# TEMPLATE_REG.net
KiCad netlist of a schematic drawn in Altium Designer
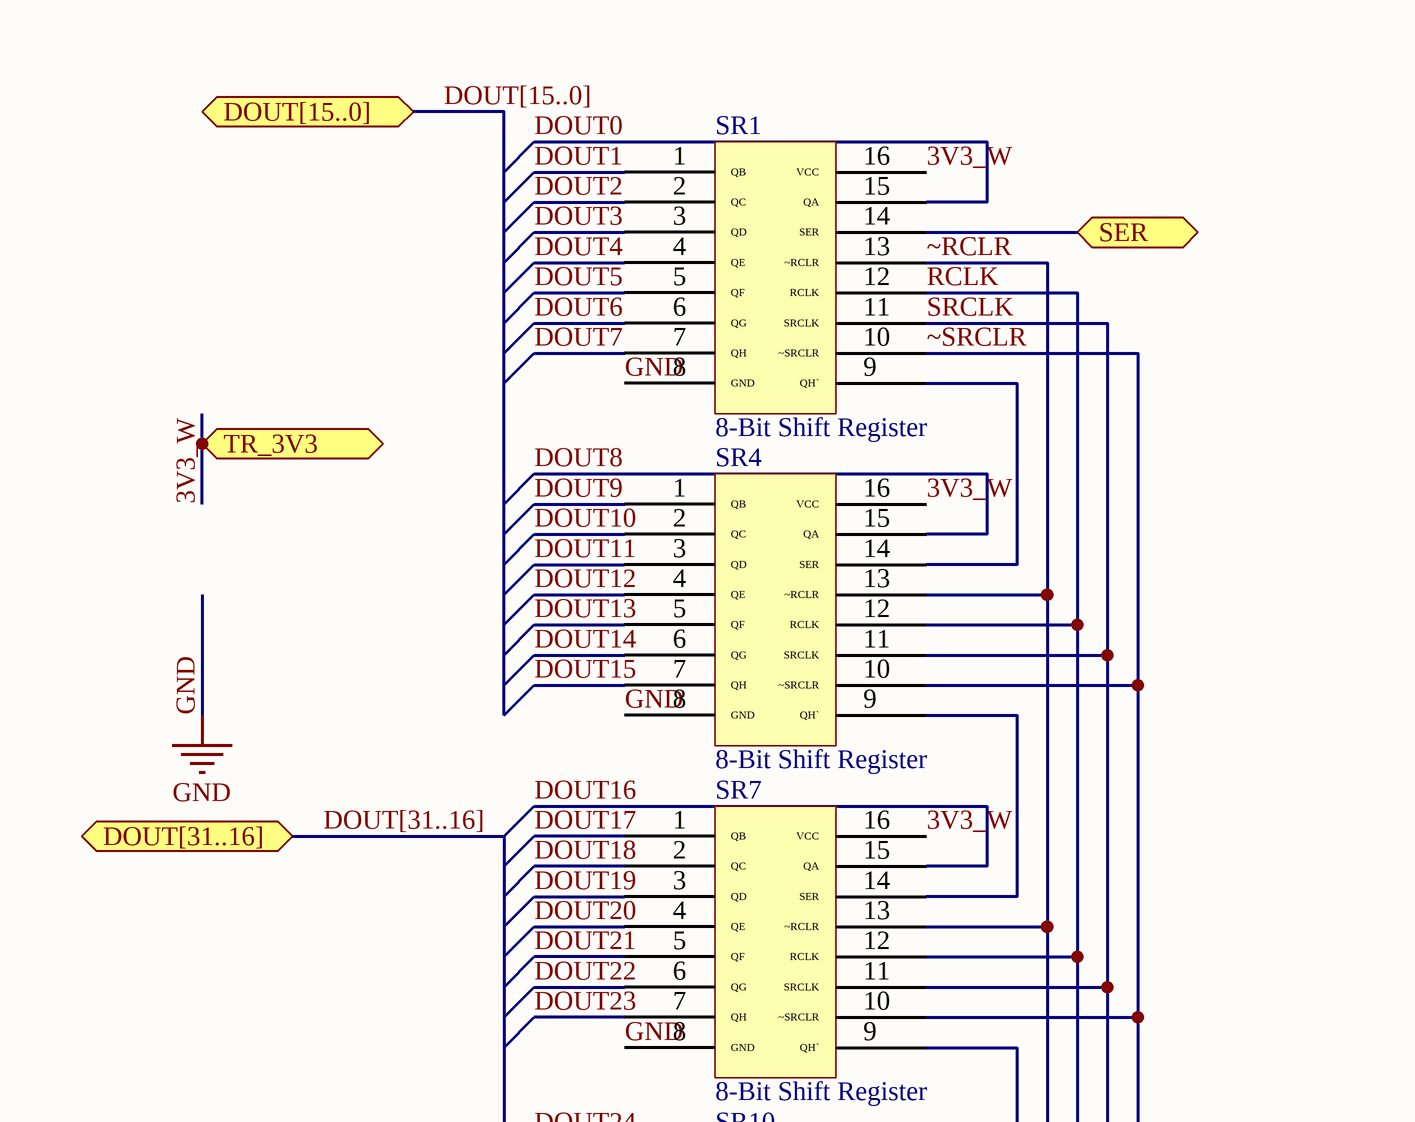
[diagram p0: TEMPLATE_REG.SchDoc, top left]
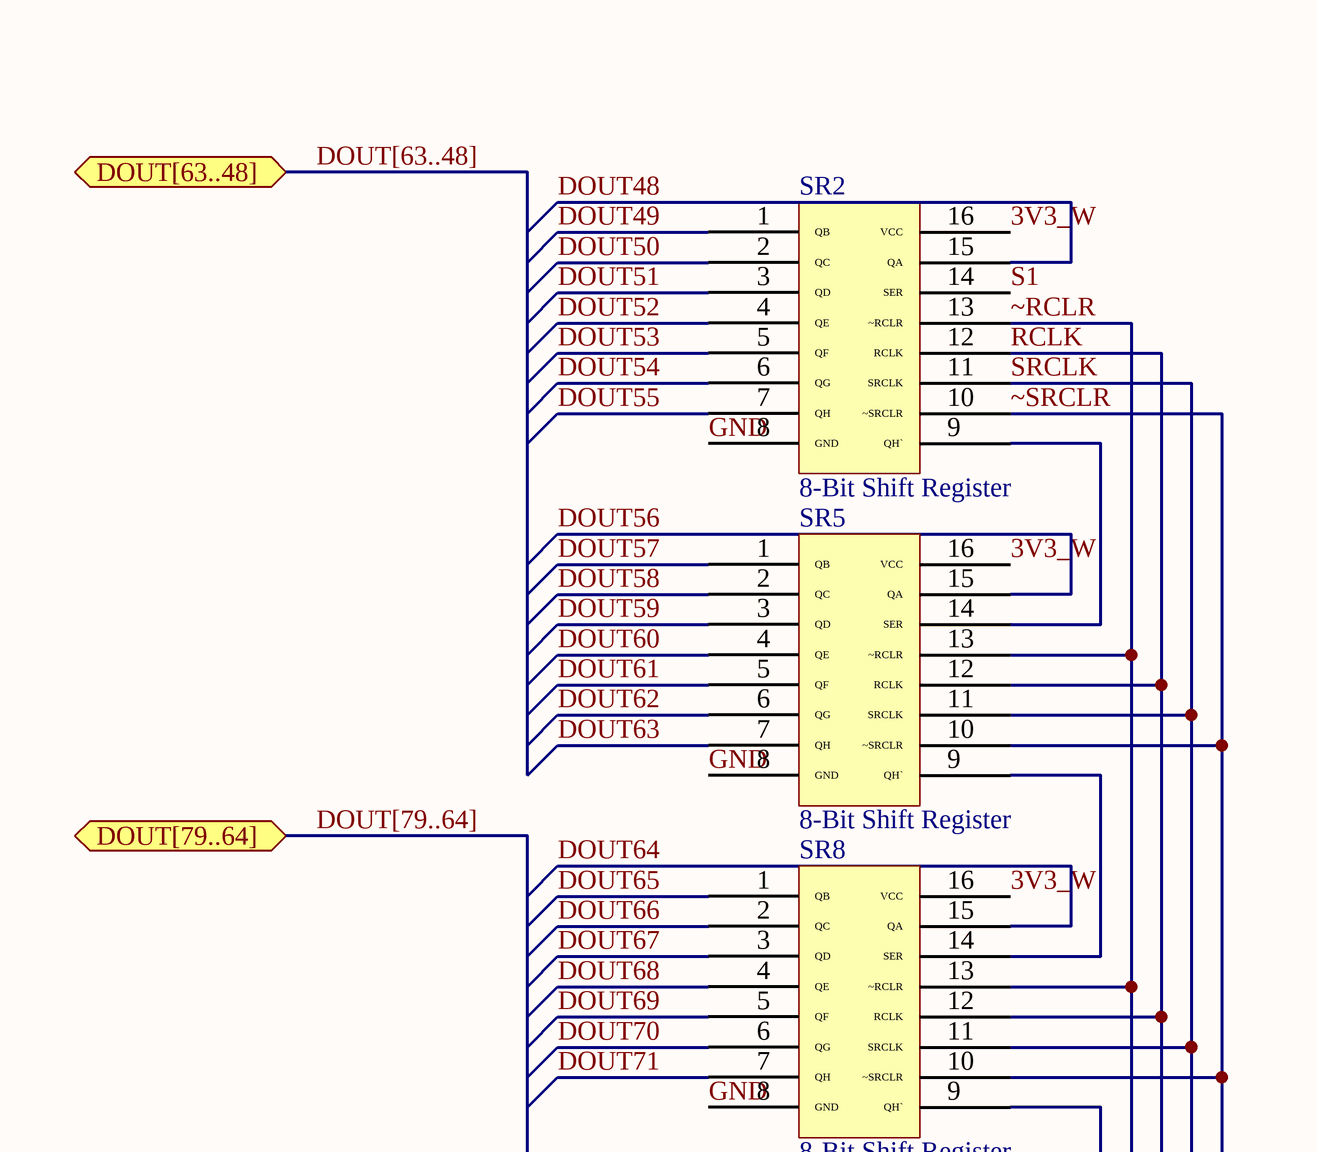
[diagram p1: TEMPLATE_REG.SchDoc, top middle]
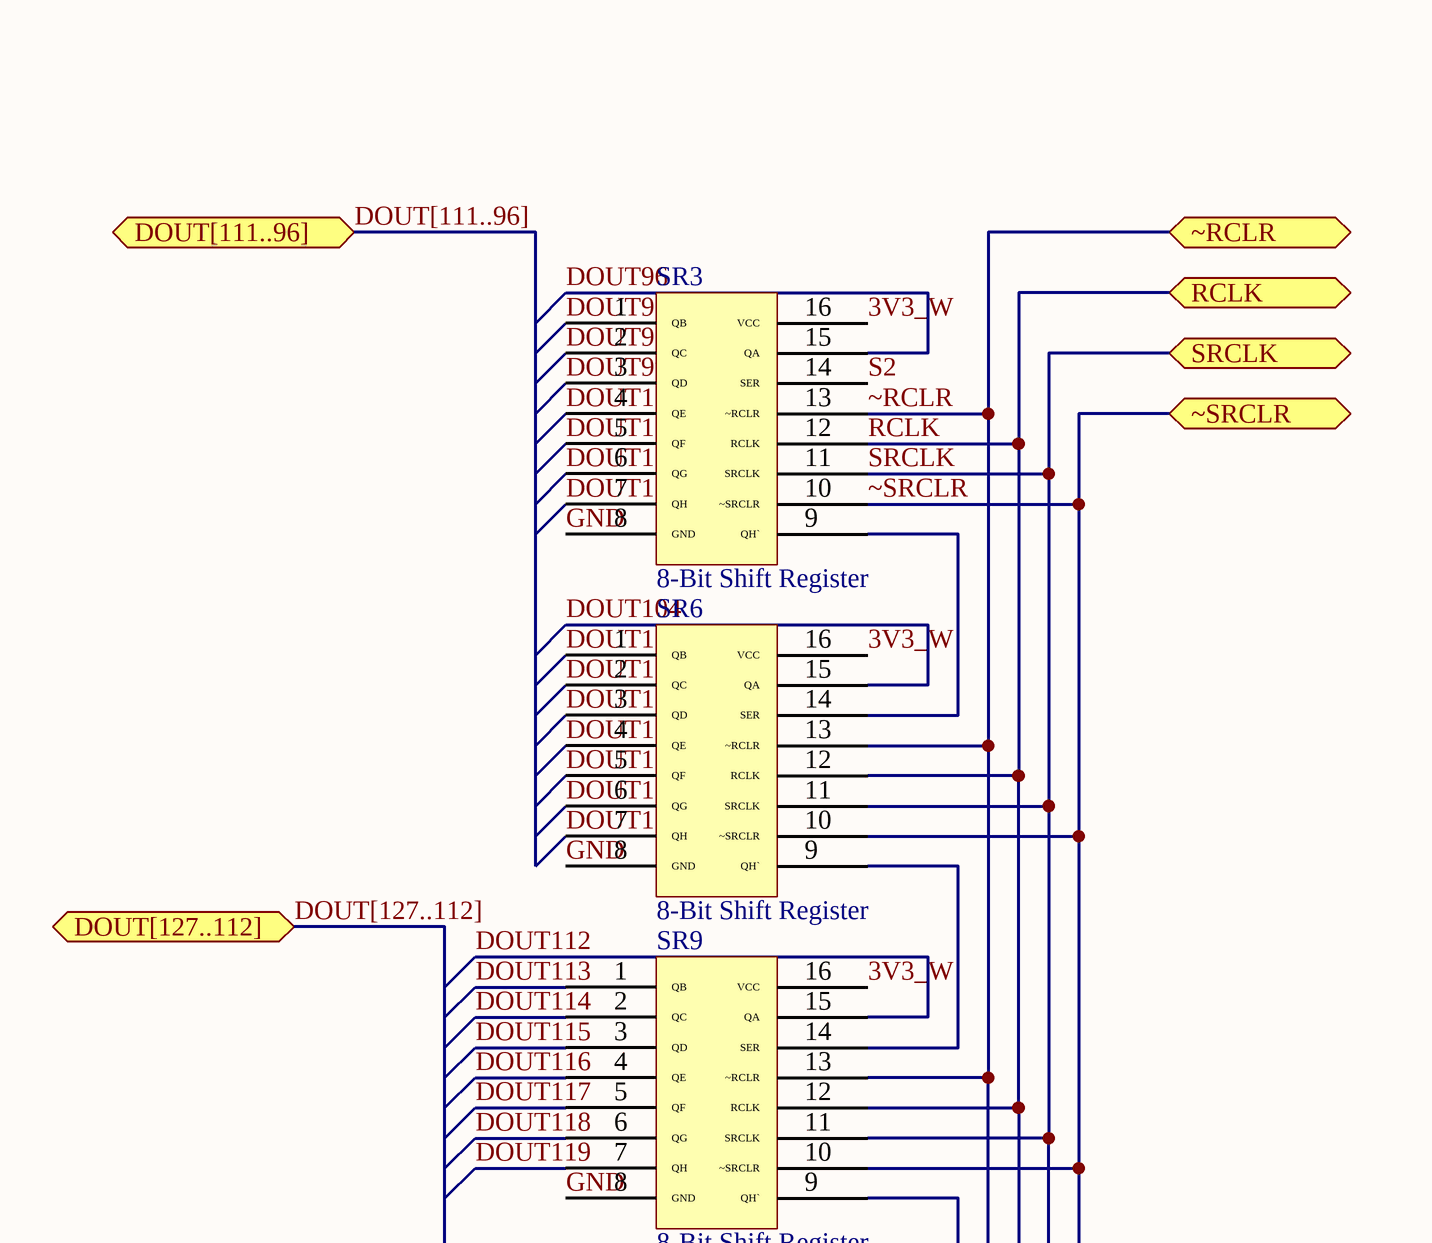
[diagram p2: TEMPLATE_REG.SchDoc, top right]
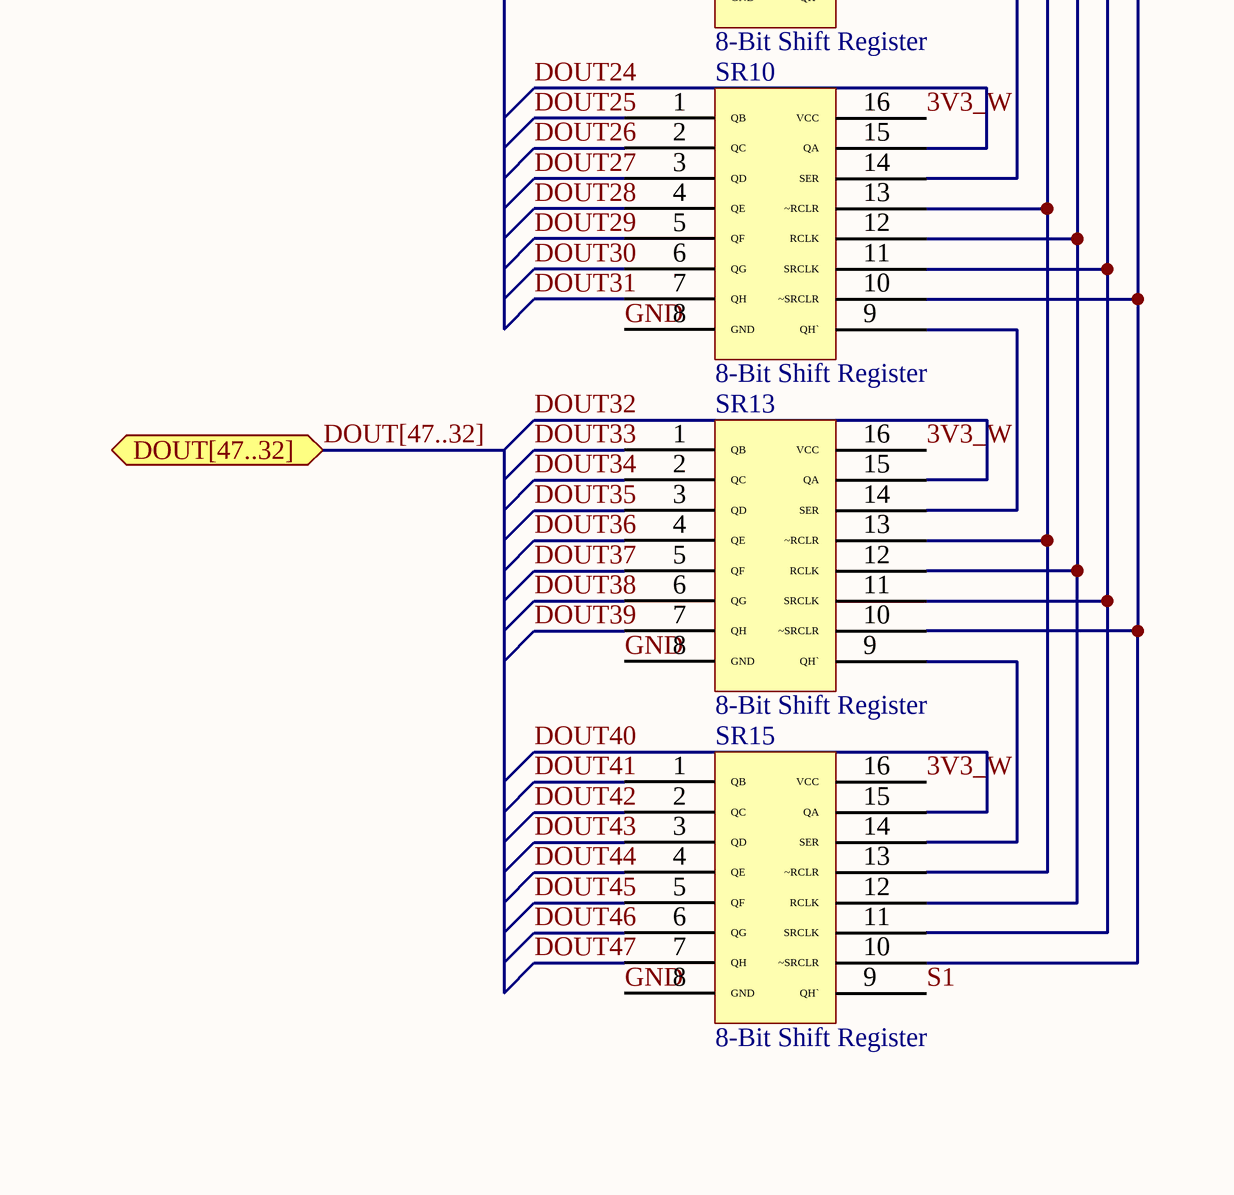
[diagram p3: TEMPLATE_REG.SchDoc, bottom left]
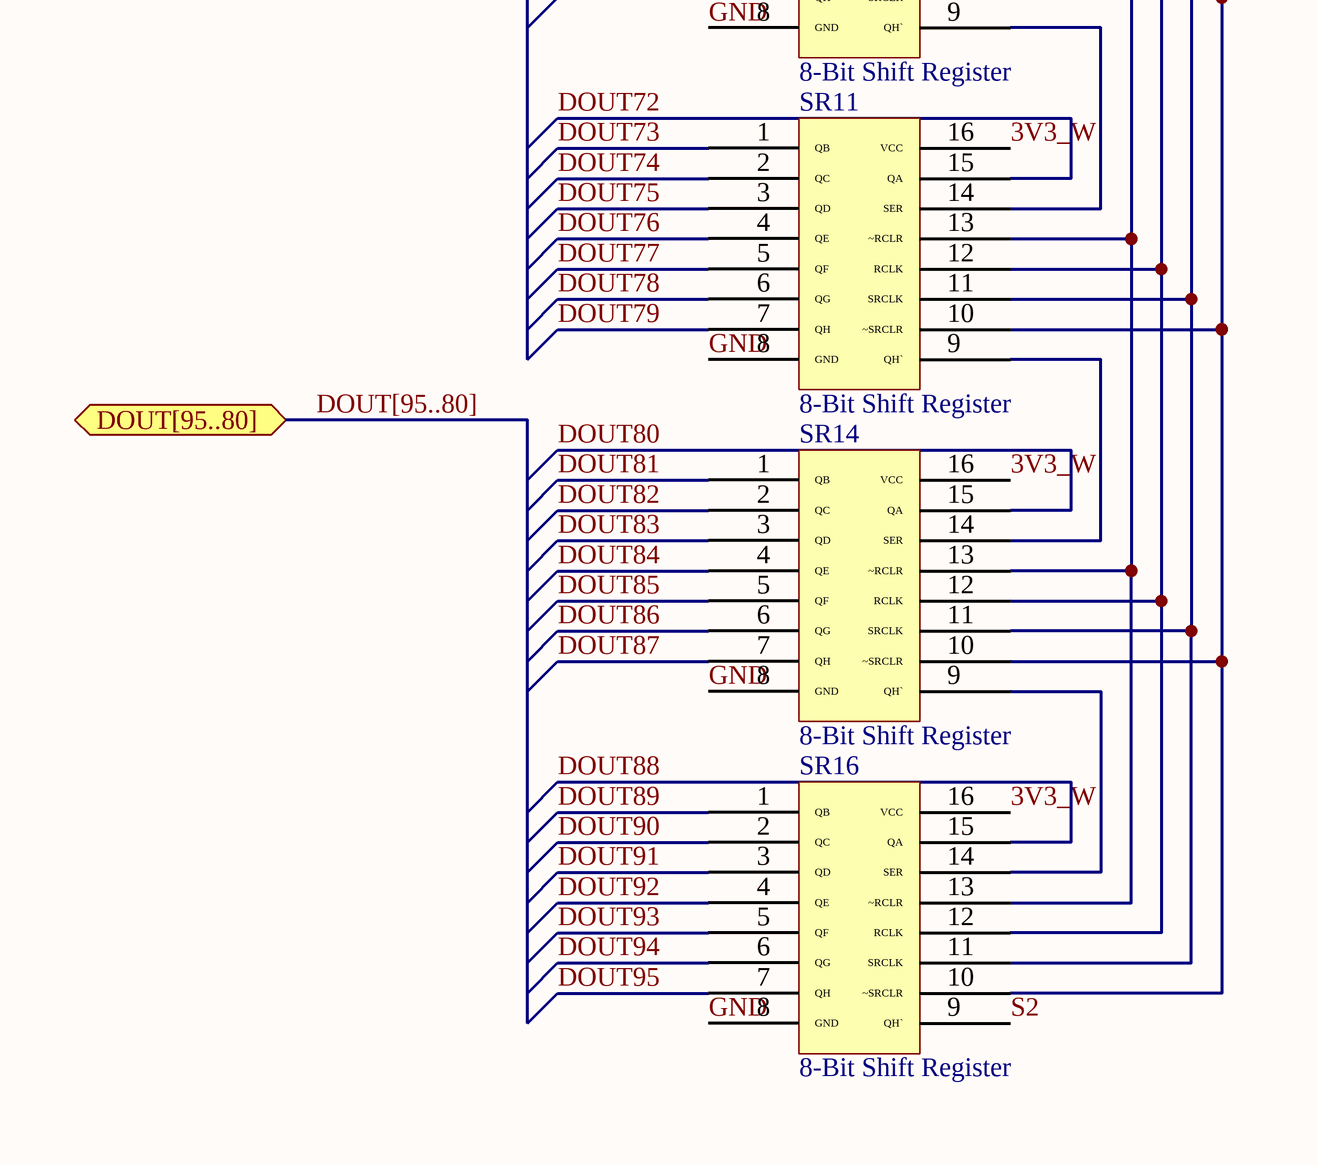
[diagram p4: TEMPLATE_REG.SchDoc, bottom middle]
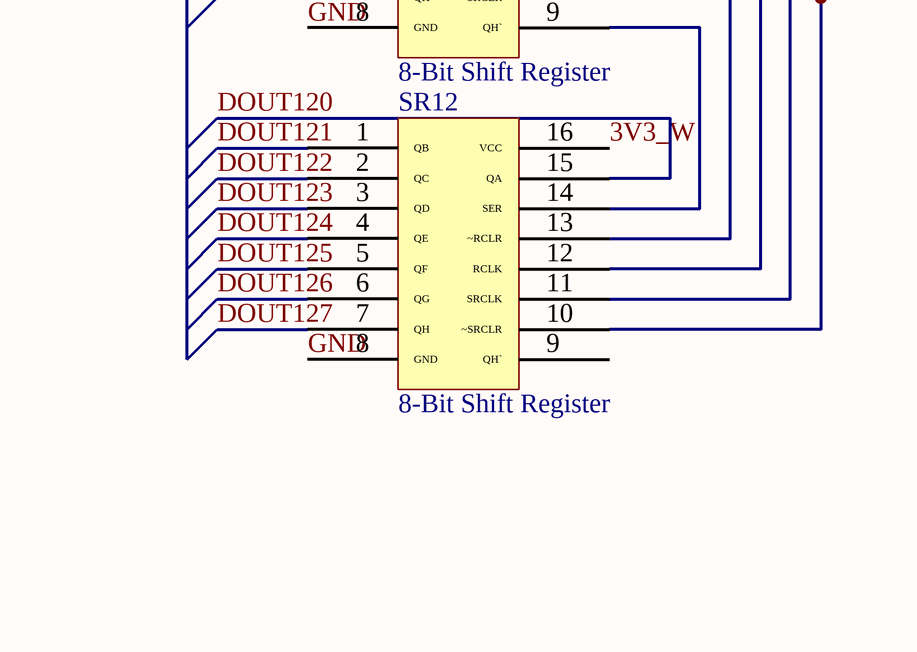
[diagram p5: TEMPLATE_REG.SchDoc, bottom right]

(export (version "E")
  (design (tool "Eeschema 10.0.6"))
  (components
    (comp (ref "SR1")
      (value "8-Bit Shift Register")
      (footprint "8-bit_shiftreg")
      (libsource (lib "BBB_Board") (part "8-Bit Shift Register"))
    )
    (comp (ref "SR2")
      (value "8-Bit Shift Register")
      (footprint "8-bit_shiftreg")
      (libsource (lib "BBB_Board") (part "8-Bit Shift Register"))
    )
    (comp (ref "SR3")
      (value "8-Bit Shift Register")
      (footprint "8-bit_shiftreg")
      (libsource (lib "BBB_Board") (part "8-Bit Shift Register"))
    )
    (comp (ref "SR4")
      (value "8-Bit Shift Register")
      (footprint "8-bit_shiftreg")
      (libsource (lib "BBB_Board") (part "8-Bit Shift Register"))
    )
    (comp (ref "SR5")
      (value "8-Bit Shift Register")
      (footprint "8-bit_shiftreg")
      (libsource (lib "BBB_Board") (part "8-Bit Shift Register"))
    )
    (comp (ref "SR6")
      (value "8-Bit Shift Register")
      (footprint "8-bit_shiftreg")
      (libsource (lib "BBB_Board") (part "8-Bit Shift Register"))
    )
    (comp (ref "SR7")
      (value "8-Bit Shift Register")
      (footprint "8-bit_shiftreg")
      (libsource (lib "BBB_Board") (part "8-Bit Shift Register"))
    )
    (comp (ref "SR8")
      (value "8-Bit Shift Register")
      (footprint "8-bit_shiftreg")
      (libsource (lib "BBB_Board") (part "8-Bit Shift Register"))
    )
    (comp (ref "SR9")
      (value "8-Bit Shift Register")
      (footprint "8-bit_shiftreg")
      (libsource (lib "BBB_Board") (part "8-Bit Shift Register"))
    )
    (comp (ref "SR10")
      (value "8-Bit Shift Register")
      (footprint "8-bit_shiftreg")
      (libsource (lib "BBB_Board") (part "8-Bit Shift Register"))
    )
    (comp (ref "SR11")
      (value "8-Bit Shift Register")
      (footprint "8-bit_shiftreg")
      (libsource (lib "BBB_Board") (part "8-Bit Shift Register"))
    )
    (comp (ref "SR12")
      (value "8-Bit Shift Register")
      (footprint "8-bit_shiftreg")
      (libsource (lib "BBB_Board") (part "8-Bit Shift Register"))
    )
    (comp (ref "SR13")
      (value "8-Bit Shift Register")
      (footprint "8-bit_shiftreg")
      (libsource (lib "BBB_Board") (part "8-Bit Shift Register"))
    )
    (comp (ref "SR14")
      (value "8-Bit Shift Register")
      (footprint "8-bit_shiftreg")
      (libsource (lib "BBB_Board") (part "8-Bit Shift Register"))
    )
    (comp (ref "SR15")
      (value "8-Bit Shift Register")
      (footprint "8-bit_shiftreg")
      (libsource (lib "BBB_Board") (part "8-Bit Shift Register"))
    )
    (comp (ref "SR16")
      (value "8-Bit Shift Register")
      (footprint "8-bit_shiftreg")
      (libsource (lib "BBB_Board") (part "8-Bit Shift Register"))
    )
  )
  (nets
    (net (code "1") (name "/3V3_W") (class "Default")
      (node (ref "SR1") (pin "16") (pinfunction "VCC_16") (pintype "passive"))
      (node (ref "SR10") (pin "16") (pinfunction "VCC_16") (pintype "passive"))
      (node (ref "SR11") (pin "16") (pinfunction "VCC_16") (pintype "passive"))
      (node (ref "SR12") (pin "16") (pinfunction "VCC_16") (pintype "passive"))
      (node (ref "SR13") (pin "16") (pinfunction "VCC_16") (pintype "passive"))
      (node (ref "SR14") (pin "16") (pinfunction "VCC_16") (pintype "passive"))
      (node (ref "SR15") (pin "16") (pinfunction "VCC_16") (pintype "passive"))
      (node (ref "SR16") (pin "16") (pinfunction "VCC_16") (pintype "passive"))
      (node (ref "SR2") (pin "16") (pinfunction "VCC_16") (pintype "passive"))
      (node (ref "SR3") (pin "16") (pinfunction "VCC_16") (pintype "passive"))
      (node (ref "SR4") (pin "16") (pinfunction "VCC_16") (pintype "passive"))
      (node (ref "SR5") (pin "16") (pinfunction "VCC_16") (pintype "passive"))
      (node (ref "SR6") (pin "16") (pinfunction "VCC_16") (pintype "passive"))
      (node (ref "SR7") (pin "16") (pinfunction "VCC_16") (pintype "passive"))
      (node (ref "SR8") (pin "16") (pinfunction "VCC_16") (pintype "passive"))
      (node (ref "SR9") (pin "16") (pinfunction "VCC_16") (pintype "passive"))
    )
    (net (code "2") (name "/DOUT0") (class "Default")
      (node (ref "SR1") (pin "15") (pinfunction "QA_15") (pintype "passive"))
    )
    (net (code "3") (name "/DOUT1") (class "Default")
      (node (ref "SR1") (pin "1") (pinfunction "QB_1") (pintype "passive"))
    )
    (net (code "4") (name "/DOUT2") (class "Default")
      (node (ref "SR1") (pin "2") (pinfunction "QC_2") (pintype "passive"))
    )
    (net (code "5") (name "/DOUT3") (class "Default")
      (node (ref "SR1") (pin "3") (pinfunction "QD_3") (pintype "passive"))
    )
    (net (code "6") (name "/DOUT4") (class "Default")
      (node (ref "SR1") (pin "4") (pinfunction "QE_4") (pintype "passive"))
    )
    (net (code "7") (name "/DOUT5") (class "Default")
      (node (ref "SR1") (pin "5") (pinfunction "QF_5") (pintype "passive"))
    )
    (net (code "8") (name "/DOUT6") (class "Default")
      (node (ref "SR1") (pin "6") (pinfunction "QG_6") (pintype "passive"))
    )
    (net (code "9") (name "/DOUT7") (class "Default")
      (node (ref "SR1") (pin "7") (pinfunction "QH_7") (pintype "passive"))
    )
    (net (code "10") (name "/DOUT8") (class "Default")
      (node (ref "SR4") (pin "15") (pinfunction "QA_15") (pintype "passive"))
    )
    (net (code "11") (name "/DOUT9") (class "Default")
      (node (ref "SR4") (pin "1") (pinfunction "QB_1") (pintype "passive"))
    )
    (net (code "12") (name "/DOUT10") (class "Default")
      (node (ref "SR4") (pin "2") (pinfunction "QC_2") (pintype "passive"))
    )
    (net (code "13") (name "/DOUT11") (class "Default")
      (node (ref "SR4") (pin "3") (pinfunction "QD_3") (pintype "passive"))
    )
    (net (code "14") (name "/DOUT12") (class "Default")
      (node (ref "SR4") (pin "4") (pinfunction "QE_4") (pintype "passive"))
    )
    (net (code "15") (name "/DOUT13") (class "Default")
      (node (ref "SR4") (pin "5") (pinfunction "QF_5") (pintype "passive"))
    )
    (net (code "16") (name "/DOUT14") (class "Default")
      (node (ref "SR4") (pin "6") (pinfunction "QG_6") (pintype "passive"))
    )
    (net (code "17") (name "/DOUT15") (class "Default")
      (node (ref "SR4") (pin "7") (pinfunction "QH_7") (pintype "passive"))
    )
    (net (code "18") (name "/DOUT16") (class "Default")
      (node (ref "SR7") (pin "15") (pinfunction "QA_15") (pintype "passive"))
    )
    (net (code "19") (name "/DOUT17") (class "Default")
      (node (ref "SR7") (pin "1") (pinfunction "QB_1") (pintype "passive"))
    )
    (net (code "20") (name "/DOUT18") (class "Default")
      (node (ref "SR7") (pin "2") (pinfunction "QC_2") (pintype "passive"))
    )
    (net (code "21") (name "/DOUT19") (class "Default")
      (node (ref "SR7") (pin "3") (pinfunction "QD_3") (pintype "passive"))
    )
    (net (code "22") (name "/DOUT20") (class "Default")
      (node (ref "SR7") (pin "4") (pinfunction "QE_4") (pintype "passive"))
    )
    (net (code "23") (name "/DOUT21") (class "Default")
      (node (ref "SR7") (pin "5") (pinfunction "QF_5") (pintype "passive"))
    )
    (net (code "24") (name "/DOUT22") (class "Default")
      (node (ref "SR7") (pin "6") (pinfunction "QG_6") (pintype "passive"))
    )
    (net (code "25") (name "/DOUT23") (class "Default")
      (node (ref "SR7") (pin "7") (pinfunction "QH_7") (pintype "passive"))
    )
    (net (code "26") (name "/DOUT24") (class "Default")
      (node (ref "SR10") (pin "15") (pinfunction "QA_15") (pintype "passive"))
    )
    (net (code "27") (name "/DOUT25") (class "Default")
      (node (ref "SR10") (pin "1") (pinfunction "QB_1") (pintype "passive"))
    )
    (net (code "28") (name "/DOUT26") (class "Default")
      (node (ref "SR10") (pin "2") (pinfunction "QC_2") (pintype "passive"))
    )
    (net (code "29") (name "/DOUT27") (class "Default")
      (node (ref "SR10") (pin "3") (pinfunction "QD_3") (pintype "passive"))
    )
    (net (code "30") (name "/DOUT28") (class "Default")
      (node (ref "SR10") (pin "4") (pinfunction "QE_4") (pintype "passive"))
    )
    (net (code "31") (name "/DOUT29") (class "Default")
      (node (ref "SR10") (pin "5") (pinfunction "QF_5") (pintype "passive"))
    )
    (net (code "32") (name "/DOUT30") (class "Default")
      (node (ref "SR10") (pin "6") (pinfunction "QG_6") (pintype "passive"))
    )
    (net (code "33") (name "/DOUT31") (class "Default")
      (node (ref "SR10") (pin "7") (pinfunction "QH_7") (pintype "passive"))
    )
    (net (code "34") (name "/DOUT32") (class "Default")
      (node (ref "SR13") (pin "15") (pinfunction "QA_15") (pintype "passive"))
    )
    (net (code "35") (name "/DOUT33") (class "Default")
      (node (ref "SR13") (pin "1") (pinfunction "QB_1") (pintype "passive"))
    )
    (net (code "36") (name "/DOUT34") (class "Default")
      (node (ref "SR13") (pin "2") (pinfunction "QC_2") (pintype "passive"))
    )
    (net (code "37") (name "/DOUT35") (class "Default")
      (node (ref "SR13") (pin "3") (pinfunction "QD_3") (pintype "passive"))
    )
    (net (code "38") (name "/DOUT36") (class "Default")
      (node (ref "SR13") (pin "4") (pinfunction "QE_4") (pintype "passive"))
    )
    (net (code "39") (name "/DOUT37") (class "Default")
      (node (ref "SR13") (pin "5") (pinfunction "QF_5") (pintype "passive"))
    )
    (net (code "40") (name "/DOUT38") (class "Default")
      (node (ref "SR13") (pin "6") (pinfunction "QG_6") (pintype "passive"))
    )
    (net (code "41") (name "/DOUT39") (class "Default")
      (node (ref "SR13") (pin "7") (pinfunction "QH_7") (pintype "passive"))
    )
    (net (code "42") (name "/DOUT40") (class "Default")
      (node (ref "SR15") (pin "15") (pinfunction "QA_15") (pintype "passive"))
    )
    (net (code "43") (name "/DOUT41") (class "Default")
      (node (ref "SR15") (pin "1") (pinfunction "QB_1") (pintype "passive"))
    )
    (net (code "44") (name "/DOUT42") (class "Default")
      (node (ref "SR15") (pin "2") (pinfunction "QC_2") (pintype "passive"))
    )
    (net (code "45") (name "/DOUT43") (class "Default")
      (node (ref "SR15") (pin "3") (pinfunction "QD_3") (pintype "passive"))
    )
    (net (code "46") (name "/DOUT44") (class "Default")
      (node (ref "SR15") (pin "4") (pinfunction "QE_4") (pintype "passive"))
    )
    (net (code "47") (name "/DOUT45") (class "Default")
      (node (ref "SR15") (pin "5") (pinfunction "QF_5") (pintype "passive"))
    )
    (net (code "48") (name "/DOUT46") (class "Default")
      (node (ref "SR15") (pin "6") (pinfunction "QG_6") (pintype "passive"))
    )
    (net (code "49") (name "/DOUT47") (class "Default")
      (node (ref "SR15") (pin "7") (pinfunction "QH_7") (pintype "passive"))
    )
    (net (code "50") (name "/DOUT48") (class "Default")
      (node (ref "SR2") (pin "15") (pinfunction "QA_15") (pintype "passive"))
    )
    (net (code "51") (name "/DOUT49") (class "Default")
      (node (ref "SR2") (pin "1") (pinfunction "QB_1") (pintype "passive"))
    )
    (net (code "52") (name "/DOUT50") (class "Default")
      (node (ref "SR2") (pin "2") (pinfunction "QC_2") (pintype "passive"))
    )
    (net (code "53") (name "/DOUT51") (class "Default")
      (node (ref "SR2") (pin "3") (pinfunction "QD_3") (pintype "passive"))
    )
    (net (code "54") (name "/DOUT52") (class "Default")
      (node (ref "SR2") (pin "4") (pinfunction "QE_4") (pintype "passive"))
    )
    (net (code "55") (name "/DOUT53") (class "Default")
      (node (ref "SR2") (pin "5") (pinfunction "QF_5") (pintype "passive"))
    )
    (net (code "56") (name "/DOUT54") (class "Default")
      (node (ref "SR2") (pin "6") (pinfunction "QG_6") (pintype "passive"))
    )
    (net (code "57") (name "/DOUT55") (class "Default")
      (node (ref "SR2") (pin "7") (pinfunction "QH_7") (pintype "passive"))
    )
    (net (code "58") (name "/DOUT56") (class "Default")
      (node (ref "SR5") (pin "15") (pinfunction "QA_15") (pintype "passive"))
    )
    (net (code "59") (name "/DOUT57") (class "Default")
      (node (ref "SR5") (pin "1") (pinfunction "QB_1") (pintype "passive"))
    )
    (net (code "60") (name "/DOUT58") (class "Default")
      (node (ref "SR5") (pin "2") (pinfunction "QC_2") (pintype "passive"))
    )
    (net (code "61") (name "/DOUT59") (class "Default")
      (node (ref "SR5") (pin "3") (pinfunction "QD_3") (pintype "passive"))
    )
    (net (code "62") (name "/DOUT60") (class "Default")
      (node (ref "SR5") (pin "4") (pinfunction "QE_4") (pintype "passive"))
    )
    (net (code "63") (name "/DOUT61") (class "Default")
      (node (ref "SR5") (pin "5") (pinfunction "QF_5") (pintype "passive"))
    )
    (net (code "64") (name "/DOUT62") (class "Default")
      (node (ref "SR5") (pin "6") (pinfunction "QG_6") (pintype "passive"))
    )
    (net (code "65") (name "/DOUT63") (class "Default")
      (node (ref "SR5") (pin "7") (pinfunction "QH_7") (pintype "passive"))
    )
    (net (code "66") (name "/DOUT64") (class "Default")
      (node (ref "SR8") (pin "15") (pinfunction "QA_15") (pintype "passive"))
    )
    (net (code "67") (name "/DOUT65") (class "Default")
      (node (ref "SR8") (pin "1") (pinfunction "QB_1") (pintype "passive"))
    )
    (net (code "68") (name "/DOUT66") (class "Default")
      (node (ref "SR8") (pin "2") (pinfunction "QC_2") (pintype "passive"))
    )
    (net (code "69") (name "/DOUT67") (class "Default")
      (node (ref "SR8") (pin "3") (pinfunction "QD_3") (pintype "passive"))
    )
    (net (code "70") (name "/DOUT68") (class "Default")
      (node (ref "SR8") (pin "4") (pinfunction "QE_4") (pintype "passive"))
    )
    (net (code "71") (name "/DOUT69") (class "Default")
      (node (ref "SR8") (pin "5") (pinfunction "QF_5") (pintype "passive"))
    )
    (net (code "72") (name "/DOUT70") (class "Default")
      (node (ref "SR8") (pin "6") (pinfunction "QG_6") (pintype "passive"))
    )
    (net (code "73") (name "/DOUT71") (class "Default")
      (node (ref "SR8") (pin "7") (pinfunction "QH_7") (pintype "passive"))
    )
    (net (code "74") (name "/DOUT72") (class "Default")
      (node (ref "SR11") (pin "15") (pinfunction "QA_15") (pintype "passive"))
    )
    (net (code "75") (name "/DOUT73") (class "Default")
      (node (ref "SR11") (pin "1") (pinfunction "QB_1") (pintype "passive"))
    )
    (net (code "76") (name "/DOUT74") (class "Default")
      (node (ref "SR11") (pin "2") (pinfunction "QC_2") (pintype "passive"))
    )
    (net (code "77") (name "/DOUT75") (class "Default")
      (node (ref "SR11") (pin "3") (pinfunction "QD_3") (pintype "passive"))
    )
    (net (code "78") (name "/DOUT76") (class "Default")
      (node (ref "SR11") (pin "4") (pinfunction "QE_4") (pintype "passive"))
    )
    (net (code "79") (name "/DOUT77") (class "Default")
      (node (ref "SR11") (pin "5") (pinfunction "QF_5") (pintype "passive"))
    )
    (net (code "80") (name "/DOUT78") (class "Default")
      (node (ref "SR11") (pin "6") (pinfunction "QG_6") (pintype "passive"))
    )
    (net (code "81") (name "/DOUT79") (class "Default")
      (node (ref "SR11") (pin "7") (pinfunction "QH_7") (pintype "passive"))
    )
    (net (code "82") (name "/DOUT80") (class "Default")
      (node (ref "SR14") (pin "15") (pinfunction "QA_15") (pintype "passive"))
    )
    (net (code "83") (name "/DOUT81") (class "Default")
      (node (ref "SR14") (pin "1") (pinfunction "QB_1") (pintype "passive"))
    )
    (net (code "84") (name "/DOUT82") (class "Default")
      (node (ref "SR14") (pin "2") (pinfunction "QC_2") (pintype "passive"))
    )
    (net (code "85") (name "/DOUT83") (class "Default")
      (node (ref "SR14") (pin "3") (pinfunction "QD_3") (pintype "passive"))
    )
    (net (code "86") (name "/DOUT84") (class "Default")
      (node (ref "SR14") (pin "4") (pinfunction "QE_4") (pintype "passive"))
    )
    (net (code "87") (name "/DOUT85") (class "Default")
      (node (ref "SR14") (pin "5") (pinfunction "QF_5") (pintype "passive"))
    )
    (net (code "88") (name "/DOUT86") (class "Default")
      (node (ref "SR14") (pin "6") (pinfunction "QG_6") (pintype "passive"))
    )
    (net (code "89") (name "/DOUT87") (class "Default")
      (node (ref "SR14") (pin "7") (pinfunction "QH_7") (pintype "passive"))
    )
    (net (code "90") (name "/DOUT88") (class "Default")
      (node (ref "SR16") (pin "15") (pinfunction "QA_15") (pintype "passive"))
    )
    (net (code "91") (name "/DOUT89") (class "Default")
      (node (ref "SR16") (pin "1") (pinfunction "QB_1") (pintype "passive"))
    )
    (net (code "92") (name "/DOUT90") (class "Default")
      (node (ref "SR16") (pin "2") (pinfunction "QC_2") (pintype "passive"))
    )
    (net (code "93") (name "/DOUT91") (class "Default")
      (node (ref "SR16") (pin "3") (pinfunction "QD_3") (pintype "passive"))
    )
    (net (code "94") (name "/DOUT92") (class "Default")
      (node (ref "SR16") (pin "4") (pinfunction "QE_4") (pintype "passive"))
    )
    (net (code "95") (name "/DOUT93") (class "Default")
      (node (ref "SR16") (pin "5") (pinfunction "QF_5") (pintype "passive"))
    )
    (net (code "96") (name "/DOUT94") (class "Default")
      (node (ref "SR16") (pin "6") (pinfunction "QG_6") (pintype "passive"))
    )
    (net (code "97") (name "/DOUT95") (class "Default")
      (node (ref "SR16") (pin "7") (pinfunction "QH_7") (pintype "passive"))
    )
    (net (code "98") (name "/DOUT96") (class "Default")
      (node (ref "SR3") (pin "15") (pinfunction "QA_15") (pintype "passive"))
    )
    (net (code "99") (name "/DOUT97") (class "Default")
      (node (ref "SR3") (pin "1") (pinfunction "QB_1") (pintype "passive"))
    )
    (net (code "100") (name "/DOUT98") (class "Default")
      (node (ref "SR3") (pin "2") (pinfunction "QC_2") (pintype "passive"))
    )
    (net (code "101") (name "/DOUT99") (class "Default")
      (node (ref "SR3") (pin "3") (pinfunction "QD_3") (pintype "passive"))
    )
    (net (code "102") (name "/DOUT100") (class "Default")
      (node (ref "SR3") (pin "4") (pinfunction "QE_4") (pintype "passive"))
    )
    (net (code "103") (name "/DOUT101") (class "Default")
      (node (ref "SR3") (pin "5") (pinfunction "QF_5") (pintype "passive"))
    )
    (net (code "104") (name "/DOUT102") (class "Default")
      (node (ref "SR3") (pin "6") (pinfunction "QG_6") (pintype "passive"))
    )
    (net (code "105") (name "/DOUT103") (class "Default")
      (node (ref "SR3") (pin "7") (pinfunction "QH_7") (pintype "passive"))
    )
    (net (code "106") (name "/DOUT104") (class "Default")
      (node (ref "SR6") (pin "15") (pinfunction "QA_15") (pintype "passive"))
    )
    (net (code "107") (name "/DOUT105") (class "Default")
      (node (ref "SR6") (pin "1") (pinfunction "QB_1") (pintype "passive"))
    )
    (net (code "108") (name "/DOUT106") (class "Default")
      (node (ref "SR6") (pin "2") (pinfunction "QC_2") (pintype "passive"))
    )
    (net (code "109") (name "/DOUT107") (class "Default")
      (node (ref "SR6") (pin "3") (pinfunction "QD_3") (pintype "passive"))
    )
    (net (code "110") (name "/DOUT108") (class "Default")
      (node (ref "SR6") (pin "4") (pinfunction "QE_4") (pintype "passive"))
    )
    (net (code "111") (name "/DOUT109") (class "Default")
      (node (ref "SR6") (pin "5") (pinfunction "QF_5") (pintype "passive"))
    )
    (net (code "112") (name "/DOUT110") (class "Default")
      (node (ref "SR6") (pin "6") (pinfunction "QG_6") (pintype "passive"))
    )
    (net (code "113") (name "/DOUT111") (class "Default")
      (node (ref "SR6") (pin "7") (pinfunction "QH_7") (pintype "passive"))
    )
    (net (code "114") (name "/DOUT112") (class "Default")
      (node (ref "SR9") (pin "15") (pinfunction "QA_15") (pintype "passive"))
    )
    (net (code "115") (name "/DOUT113") (class "Default")
      (node (ref "SR9") (pin "1") (pinfunction "QB_1") (pintype "passive"))
    )
    (net (code "116") (name "/DOUT114") (class "Default")
      (node (ref "SR9") (pin "2") (pinfunction "QC_2") (pintype "passive"))
    )
    (net (code "117") (name "/DOUT115") (class "Default")
      (node (ref "SR9") (pin "3") (pinfunction "QD_3") (pintype "passive"))
    )
    (net (code "118") (name "/DOUT116") (class "Default")
      (node (ref "SR9") (pin "4") (pinfunction "QE_4") (pintype "passive"))
    )
    (net (code "119") (name "/DOUT117") (class "Default")
      (node (ref "SR9") (pin "5") (pinfunction "QF_5") (pintype "passive"))
    )
    (net (code "120") (name "/DOUT118") (class "Default")
      (node (ref "SR9") (pin "6") (pinfunction "QG_6") (pintype "passive"))
    )
    (net (code "121") (name "/DOUT119") (class "Default")
      (node (ref "SR9") (pin "7") (pinfunction "QH_7") (pintype "passive"))
    )
    (net (code "122") (name "/DOUT120") (class "Default")
      (node (ref "SR12") (pin "15") (pinfunction "QA_15") (pintype "passive"))
    )
    (net (code "123") (name "/DOUT121") (class "Default")
      (node (ref "SR12") (pin "1") (pinfunction "QB_1") (pintype "passive"))
    )
    (net (code "124") (name "/DOUT122") (class "Default")
      (node (ref "SR12") (pin "2") (pinfunction "QC_2") (pintype "passive"))
    )
    (net (code "125") (name "/DOUT123") (class "Default")
      (node (ref "SR12") (pin "3") (pinfunction "QD_3") (pintype "passive"))
    )
    (net (code "126") (name "/DOUT124") (class "Default")
      (node (ref "SR12") (pin "4") (pinfunction "QE_4") (pintype "passive"))
    )
    (net (code "127") (name "/DOUT125") (class "Default")
      (node (ref "SR12") (pin "5") (pinfunction "QF_5") (pintype "passive"))
    )
    (net (code "128") (name "/DOUT126") (class "Default")
      (node (ref "SR12") (pin "6") (pinfunction "QG_6") (pintype "passive"))
    )
    (net (code "129") (name "/DOUT127") (class "Default")
      (node (ref "SR12") (pin "7") (pinfunction "QH_7") (pintype "passive"))
    )
    (net (code "138") (name "/RCLK") (class "Default")
      (node (ref "SR1") (pin "12") (pinfunction "RCLK_12") (pintype "passive"))
      (node (ref "SR10") (pin "12") (pinfunction "RCLK_12") (pintype "passive"))
      (node (ref "SR11") (pin "12") (pinfunction "RCLK_12") (pintype "passive"))
      (node (ref "SR12") (pin "12") (pinfunction "RCLK_12") (pintype "passive"))
      (node (ref "SR13") (pin "12") (pinfunction "RCLK_12") (pintype "passive"))
      (node (ref "SR14") (pin "12") (pinfunction "RCLK_12") (pintype "passive"))
      (node (ref "SR15") (pin "12") (pinfunction "RCLK_12") (pintype "passive"))
      (node (ref "SR16") (pin "12") (pinfunction "RCLK_12") (pintype "passive"))
      (node (ref "SR2") (pin "12") (pinfunction "RCLK_12") (pintype "passive"))
      (node (ref "SR3") (pin "12") (pinfunction "RCLK_12") (pintype "passive"))
      (node (ref "SR4") (pin "12") (pinfunction "RCLK_12") (pintype "passive"))
      (node (ref "SR5") (pin "12") (pinfunction "RCLK_12") (pintype "passive"))
      (node (ref "SR6") (pin "12") (pinfunction "RCLK_12") (pintype "passive"))
      (node (ref "SR7") (pin "12") (pinfunction "RCLK_12") (pintype "passive"))
      (node (ref "SR8") (pin "12") (pinfunction "RCLK_12") (pintype "passive"))
      (node (ref "SR9") (pin "12") (pinfunction "RCLK_12") (pintype "passive"))
    )
    (net (code "139") (name "/S1") (class "Default")
      (node (ref "SR15") (pin "9") (pinfunction "QH`_9") (pintype "passive"))
      (node (ref "SR2") (pin "14") (pinfunction "SER_14") (pintype "passive"))
    )
    (net (code "140") (name "/S2") (class "Default")
      (node (ref "SR16") (pin "9") (pinfunction "QH`_9") (pintype "passive"))
      (node (ref "SR3") (pin "14") (pinfunction "SER_14") (pintype "passive"))
    )
    (net (code "141") (name "/SER") (class "Default")
      (node (ref "SR1") (pin "14") (pinfunction "SER_14") (pintype "passive"))
    )
    (net (code "142") (name "/SRCLK") (class "Default")
      (node (ref "SR1") (pin "11") (pinfunction "SRCLK_11") (pintype "passive"))
      (node (ref "SR10") (pin "11") (pinfunction "SRCLK_11") (pintype "passive"))
      (node (ref "SR11") (pin "11") (pinfunction "SRCLK_11") (pintype "passive"))
      (node (ref "SR12") (pin "11") (pinfunction "SRCLK_11") (pintype "passive"))
      (node (ref "SR13") (pin "11") (pinfunction "SRCLK_11") (pintype "passive"))
      (node (ref "SR14") (pin "11") (pinfunction "SRCLK_11") (pintype "passive"))
      (node (ref "SR15") (pin "11") (pinfunction "SRCLK_11") (pintype "passive"))
      (node (ref "SR16") (pin "11") (pinfunction "SRCLK_11") (pintype "passive"))
      (node (ref "SR2") (pin "11") (pinfunction "SRCLK_11") (pintype "passive"))
      (node (ref "SR3") (pin "11") (pinfunction "SRCLK_11") (pintype "passive"))
      (node (ref "SR4") (pin "11") (pinfunction "SRCLK_11") (pintype "passive"))
      (node (ref "SR5") (pin "11") (pinfunction "SRCLK_11") (pintype "passive"))
      (node (ref "SR6") (pin "11") (pinfunction "SRCLK_11") (pintype "passive"))
      (node (ref "SR7") (pin "11") (pinfunction "SRCLK_11") (pintype "passive"))
      (node (ref "SR8") (pin "11") (pinfunction "SRCLK_11") (pintype "passive"))
      (node (ref "SR9") (pin "11") (pinfunction "SRCLK_11") (pintype "passive"))
    )
    (net (code "143") (name "/~RCLR") (class "Default")
      (node (ref "SR1") (pin "13") (pinfunction "~RCLR_13") (pintype "passive"))
      (node (ref "SR10") (pin "13") (pinfunction "~RCLR_13") (pintype "passive"))
      (node (ref "SR11") (pin "13") (pinfunction "~RCLR_13") (pintype "passive"))
      (node (ref "SR12") (pin "13") (pinfunction "~RCLR_13") (pintype "passive"))
      (node (ref "SR13") (pin "13") (pinfunction "~RCLR_13") (pintype "passive"))
      (node (ref "SR14") (pin "13") (pinfunction "~RCLR_13") (pintype "passive"))
      (node (ref "SR15") (pin "13") (pinfunction "~RCLR_13") (pintype "passive"))
      (node (ref "SR16") (pin "13") (pinfunction "~RCLR_13") (pintype "passive"))
      (node (ref "SR2") (pin "13") (pinfunction "~RCLR_13") (pintype "passive"))
      (node (ref "SR3") (pin "13") (pinfunction "~RCLR_13") (pintype "passive"))
      (node (ref "SR4") (pin "13") (pinfunction "~RCLR_13") (pintype "passive"))
      (node (ref "SR5") (pin "13") (pinfunction "~RCLR_13") (pintype "passive"))
      (node (ref "SR6") (pin "13") (pinfunction "~RCLR_13") (pintype "passive"))
      (node (ref "SR7") (pin "13") (pinfunction "~RCLR_13") (pintype "passive"))
      (node (ref "SR8") (pin "13") (pinfunction "~RCLR_13") (pintype "passive"))
      (node (ref "SR9") (pin "13") (pinfunction "~RCLR_13") (pintype "passive"))
    )
    (net (code "144") (name "/~SRCLR") (class "Default")
      (node (ref "SR1") (pin "10") (pinfunction "~SRCLR_10") (pintype "passive"))
      (node (ref "SR10") (pin "10") (pinfunction "~SRCLR_10") (pintype "passive"))
      (node (ref "SR11") (pin "10") (pinfunction "~SRCLR_10") (pintype "passive"))
      (node (ref "SR12") (pin "10") (pinfunction "~SRCLR_10") (pintype "passive"))
      (node (ref "SR13") (pin "10") (pinfunction "~SRCLR_10") (pintype "passive"))
      (node (ref "SR14") (pin "10") (pinfunction "~SRCLR_10") (pintype "passive"))
      (node (ref "SR15") (pin "10") (pinfunction "~SRCLR_10") (pintype "passive"))
      (node (ref "SR16") (pin "10") (pinfunction "~SRCLR_10") (pintype "passive"))
      (node (ref "SR2") (pin "10") (pinfunction "~SRCLR_10") (pintype "passive"))
      (node (ref "SR3") (pin "10") (pinfunction "~SRCLR_10") (pintype "passive"))
      (node (ref "SR4") (pin "10") (pinfunction "~SRCLR_10") (pintype "passive"))
      (node (ref "SR5") (pin "10") (pinfunction "~SRCLR_10") (pintype "passive"))
      (node (ref "SR6") (pin "10") (pinfunction "~SRCLR_10") (pintype "passive"))
      (node (ref "SR7") (pin "10") (pinfunction "~SRCLR_10") (pintype "passive"))
      (node (ref "SR8") (pin "10") (pinfunction "~SRCLR_10") (pintype "passive"))
      (node (ref "SR9") (pin "10") (pinfunction "~SRCLR_10") (pintype "passive"))
    )
    (net (code "145") (name "GND") (class "Default")
      (node (ref "SR1") (pin "8") (pinfunction "GND_8") (pintype "passive"))
      (node (ref "SR10") (pin "8") (pinfunction "GND_8") (pintype "passive"))
      (node (ref "SR11") (pin "8") (pinfunction "GND_8") (pintype "passive"))
      (node (ref "SR12") (pin "8") (pinfunction "GND_8") (pintype "passive"))
      (node (ref "SR13") (pin "8") (pinfunction "GND_8") (pintype "passive"))
      (node (ref "SR14") (pin "8") (pinfunction "GND_8") (pintype "passive"))
      (node (ref "SR15") (pin "8") (pinfunction "GND_8") (pintype "passive"))
      (node (ref "SR16") (pin "8") (pinfunction "GND_8") (pintype "passive"))
      (node (ref "SR2") (pin "8") (pinfunction "GND_8") (pintype "passive"))
      (node (ref "SR3") (pin "8") (pinfunction "GND_8") (pintype "passive"))
      (node (ref "SR4") (pin "8") (pinfunction "GND_8") (pintype "passive"))
      (node (ref "SR5") (pin "8") (pinfunction "GND_8") (pintype "passive"))
      (node (ref "SR6") (pin "8") (pinfunction "GND_8") (pintype "passive"))
      (node (ref "SR7") (pin "8") (pinfunction "GND_8") (pintype "passive"))
      (node (ref "SR8") (pin "8") (pinfunction "GND_8") (pintype "passive"))
      (node (ref "SR9") (pin "8") (pinfunction "GND_8") (pintype "passive"))
    )
    (net (code "146") (name "Net-(SR1-QH`)") (class "Default")
      (node (ref "SR1") (pin "9") (pinfunction "QH`_9") (pintype "passive"))
      (node (ref "SR4") (pin "14") (pinfunction "SER_14") (pintype "passive"))
    )
    (net (code "147") (name "Net-(SR2-QH`)") (class "Default")
      (node (ref "SR2") (pin "9") (pinfunction "QH`_9") (pintype "passive"))
      (node (ref "SR5") (pin "14") (pinfunction "SER_14") (pintype "passive"))
    )
    (net (code "148") (name "Net-(SR3-QH`)") (class "Default")
      (node (ref "SR3") (pin "9") (pinfunction "QH`_9") (pintype "passive"))
      (node (ref "SR6") (pin "14") (pinfunction "SER_14") (pintype "passive"))
    )
    (net (code "149") (name "Net-(SR4-QH`)") (class "Default")
      (node (ref "SR4") (pin "9") (pinfunction "QH`_9") (pintype "passive"))
      (node (ref "SR7") (pin "14") (pinfunction "SER_14") (pintype "passive"))
    )
    (net (code "150") (name "Net-(SR5-QH`)") (class "Default")
      (node (ref "SR5") (pin "9") (pinfunction "QH`_9") (pintype "passive"))
      (node (ref "SR8") (pin "14") (pinfunction "SER_14") (pintype "passive"))
    )
    (net (code "151") (name "Net-(SR6-QH`)") (class "Default")
      (node (ref "SR6") (pin "9") (pinfunction "QH`_9") (pintype "passive"))
      (node (ref "SR9") (pin "14") (pinfunction "SER_14") (pintype "passive"))
    )
    (net (code "152") (name "Net-(SR10-QH`)") (class "Default")
      (node (ref "SR10") (pin "9") (pinfunction "QH`_9") (pintype "passive"))
      (node (ref "SR13") (pin "14") (pinfunction "SER_14") (pintype "passive"))
    )
    (net (code "153") (name "Net-(SR10-SER)") (class "Default")
      (node (ref "SR10") (pin "14") (pinfunction "SER_14") (pintype "passive"))
      (node (ref "SR7") (pin "9") (pinfunction "QH`_9") (pintype "passive"))
    )
    (net (code "154") (name "Net-(SR11-QH`)") (class "Default")
      (node (ref "SR11") (pin "9") (pinfunction "QH`_9") (pintype "passive"))
      (node (ref "SR14") (pin "14") (pinfunction "SER_14") (pintype "passive"))
    )
    (net (code "155") (name "Net-(SR11-SER)") (class "Default")
      (node (ref "SR11") (pin "14") (pinfunction "SER_14") (pintype "passive"))
      (node (ref "SR8") (pin "9") (pinfunction "QH`_9") (pintype "passive"))
    )
    (net (code "156") (name "Net-(SR12-SER)") (class "Default")
      (node (ref "SR12") (pin "14") (pinfunction "SER_14") (pintype "passive"))
      (node (ref "SR9") (pin "9") (pinfunction "QH`_9") (pintype "passive"))
    )
    (net (code "157") (name "Net-(SR13-QH`)") (class "Default")
      (node (ref "SR13") (pin "9") (pinfunction "QH`_9") (pintype "passive"))
      (node (ref "SR15") (pin "14") (pinfunction "SER_14") (pintype "passive"))
    )
    (net (code "158") (name "Net-(SR14-QH`)") (class "Default")
      (node (ref "SR14") (pin "9") (pinfunction "QH`_9") (pintype "passive"))
      (node (ref "SR16") (pin "14") (pinfunction "SER_14") (pintype "passive"))
    )
    (net (code "159") (name "unconnected-(SR12-QH`-Pad9)") (class "Default")
      (node (ref "SR12") (pin "9") (pinfunction "QH`_9") (pintype "passive"))
    )
  )
)
